# rc13-mbed-main-board.net
KiCad netlist of a schematic drawn in EAGLE
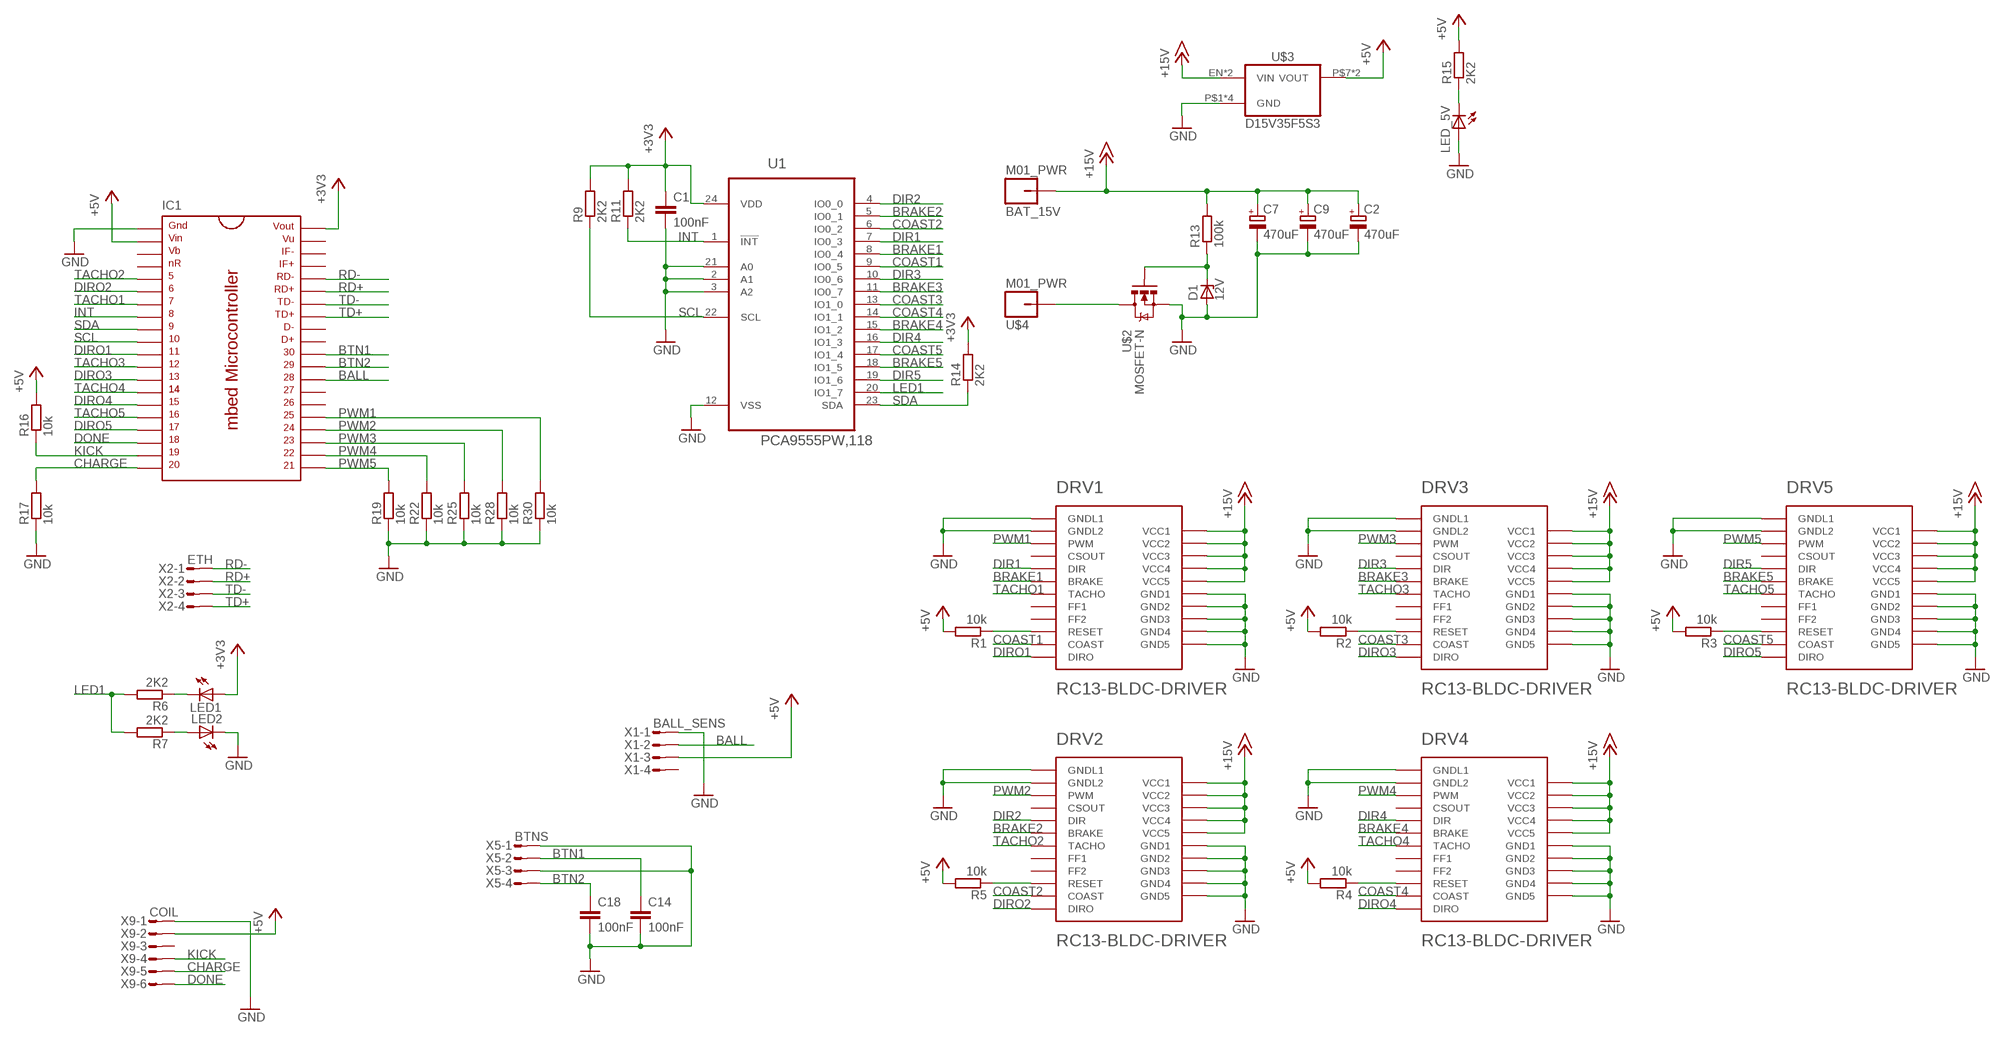
[diagram p0: schematic, sheet 1]

(export (version "E")
  (design (tool "Eeschema 10.0.6"))
  (components
    (comp (ref "BAT_15V")
      (value "M01_PWR")
      (footprint "eagle-import:PWR_HOLE")
      (libsource (lib "eagle-import") (part "M01_PWR"))
    )
    (comp (ref "C1")
      (value "100nF")
      (footprint "eagle-import:C0603K")
      (libsource (lib "eagle-import") (part "C-EUC0603K"))
    )
    (comp (ref "C2")
      (value "470uF")
      (footprint "eagle-import:E3,5-8")
      (libsource (lib "eagle-import") (part "CPOL-EUE3.5-8"))
    )
    (comp (ref "C7")
      (value "470uF")
      (footprint "eagle-import:E3,5-8")
      (libsource (lib "eagle-import") (part "CPOL-EUE3.5-8"))
    )
    (comp (ref "C9")
      (value "470uF")
      (footprint "eagle-import:E3,5-8")
      (libsource (lib "eagle-import") (part "CPOL-EUE3.5-8"))
    )
    (comp (ref "C14")
      (value "100nF")
      (footprint "eagle-import:C0603K")
      (libsource (lib "eagle-import") (part "C-EUC0603K"))
    )
    (comp (ref "C18")
      (value "100nF")
      (footprint "eagle-import:C0603K")
      (libsource (lib "eagle-import") (part "C-EUC0603K"))
    )
    (comp (ref "D1")
      (value "12V")
      (footprint "eagle-import:SOD123")
      (libsource (lib "eagle-import") (part "ZENER-DIODESOD123"))
    )
    (comp (ref "DRV1")
      (value "RC13-BLDC-DRIVER")
      (footprint "eagle-import:RC13-BLDC-DRIVER")
      (libsource (lib "eagle-import") (part "RC13-BLDC-DRIVER"))
    )
    (comp (ref "DRV2")
      (value "RC13-BLDC-DRIVER")
      (footprint "eagle-import:RC13-BLDC-DRIVER")
      (libsource (lib "eagle-import") (part "RC13-BLDC-DRIVER"))
    )
    (comp (ref "DRV3")
      (value "RC13-BLDC-DRIVER")
      (footprint "eagle-import:RC13-BLDC-DRIVER")
      (libsource (lib "eagle-import") (part "RC13-BLDC-DRIVER"))
    )
    (comp (ref "DRV4")
      (value "RC13-BLDC-DRIVER")
      (footprint "eagle-import:RC13-BLDC-DRIVER")
      (libsource (lib "eagle-import") (part "RC13-BLDC-DRIVER"))
    )
    (comp (ref "DRV5")
      (value "RC13-BLDC-DRIVER")
      (footprint "eagle-import:RC13-BLDC-DRIVER")
      (libsource (lib "eagle-import") (part "RC13-BLDC-DRIVER"))
    )
    (comp (ref "IC1")
      (value "MBED_MICROCONTROLLER")
      (footprint "eagle-import:DIL40_0.9")
      (libsource (lib "eagle-import") (part "MBED_MICROCONTROLLER"))
    )
    (comp (ref "LED1")
      (value "LEDCHIP-LED0603")
      (footprint "eagle-import:CHIP-LED0603")
      (libsource (lib "eagle-import") (part "LEDCHIP-LED0603"))
    )
    (comp (ref "LED2")
      (value "LEDCHIP-LED0603")
      (footprint "eagle-import:CHIP-LED0603")
      (libsource (lib "eagle-import") (part "LEDCHIP-LED0603"))
    )
    (comp (ref "LED_5V")
      (value "LEDCHIP-LED0603")
      (footprint "eagle-import:CHIP-LED0603")
      (libsource (lib "eagle-import") (part "LEDCHIP-LED0603"))
    )
    (comp (ref "R1")
      (value "10k")
      (footprint "eagle-import:R0603")
      (libsource (lib "eagle-import") (part "R-EU_R0603"))
    )
    (comp (ref "R2")
      (value "10k")
      (footprint "eagle-import:R0603")
      (libsource (lib "eagle-import") (part "R-EU_R0603"))
    )
    (comp (ref "R3")
      (value "10k")
      (footprint "eagle-import:R0603")
      (libsource (lib "eagle-import") (part "R-EU_R0603"))
    )
    (comp (ref "R4")
      (value "10k")
      (footprint "eagle-import:R0603")
      (libsource (lib "eagle-import") (part "R-EU_R0603"))
    )
    (comp (ref "R5")
      (value "10k")
      (footprint "eagle-import:R0603")
      (libsource (lib "eagle-import") (part "R-EU_R0603"))
    )
    (comp (ref "R6")
      (value "2K2")
      (footprint "eagle-import:R0603")
      (libsource (lib "eagle-import") (part "R-EU_R0603"))
    )
    (comp (ref "R7")
      (value "2K2")
      (footprint "eagle-import:R0603")
      (libsource (lib "eagle-import") (part "R-EU_R0603"))
    )
    (comp (ref "R9")
      (value "2K2")
      (footprint "eagle-import:R0603")
      (libsource (lib "eagle-import") (part "R-EU_R0603"))
    )
    (comp (ref "R11")
      (value "2K2")
      (footprint "eagle-import:R0603")
      (libsource (lib "eagle-import") (part "R-EU_R0603"))
    )
    (comp (ref "R13")
      (value "100k")
      (footprint "eagle-import:R0603")
      (libsource (lib "eagle-import") (part "R-EU_R0603"))
    )
    (comp (ref "R14")
      (value "2K2")
      (footprint "eagle-import:R0603")
      (libsource (lib "eagle-import") (part "R-EU_R0603"))
    )
    (comp (ref "R15")
      (value "2K2")
      (footprint "eagle-import:R0603")
      (libsource (lib "eagle-import") (part "R-EU_R0603"))
    )
    (comp (ref "R16")
      (value "10k")
      (footprint "eagle-import:R0603")
      (libsource (lib "eagle-import") (part "R-EU_R0603"))
    )
    (comp (ref "R17")
      (value "10k")
      (footprint "eagle-import:R0603")
      (libsource (lib "eagle-import") (part "R-EU_R0603"))
    )
    (comp (ref "R19")
      (value "10k")
      (footprint "eagle-import:R0603")
      (libsource (lib "eagle-import") (part "R-EU_R0603"))
    )
    (comp (ref "R22")
      (value "10k")
      (footprint "eagle-import:R0603")
      (libsource (lib "eagle-import") (part "R-EU_R0603"))
    )
    (comp (ref "R25")
      (value "10k")
      (footprint "eagle-import:R0603")
      (libsource (lib "eagle-import") (part "R-EU_R0603"))
    )
    (comp (ref "R28")
      (value "10k")
      (footprint "eagle-import:R0603")
      (libsource (lib "eagle-import") (part "R-EU_R0603"))
    )
    (comp (ref "R30")
      (value "10k")
      (footprint "eagle-import:R0603")
      (libsource (lib "eagle-import") (part "R-EU_R0603"))
    )
    (comp (ref "U$2")
      (value "MOSFET-N")
      (footprint "eagle-import:TO127P600X120-5N")
      (libsource (lib "eagle-import") (part "MOSFET-N-SOT669"))
    )
    (comp (ref "U$3")
      (value "D15V35F5S3")
      (footprint "eagle-import:D15V35F5S3")
      (libsource (lib "eagle-import") (part "D15V35F5S3"))
    )
    (comp (ref "U$4")
      (value "M01_PWR")
      (footprint "eagle-import:PWR_HOLE")
      (libsource (lib "eagle-import") (part "M01_PWR"))
    )
    (comp (ref "U1")
      (value "PCA9555PW,118")
      (footprint "eagle-import:SOP65P640X110-24N")
      (libsource (lib "eagle-import") (part "PCA9555PW,118"))
    )
    (comp (ref "X1")
      (value "BALL_SENS")
      (footprint "eagle-import:MICROMATCH-4")
      (fields (field (name "MPN") "7-215464-4"))
      (libsource (lib "eagle-import") (part "MICROMATCH-4"))
    )
    (comp (ref "X2")
      (value "ETH")
      (footprint "eagle-import:MICROMATCH-4")
      (fields (field (name "MPN") "7-215464-4"))
      (libsource (lib "eagle-import") (part "MICROMATCH-4"))
    )
    (comp (ref "X5")
      (value "BTNS")
      (footprint "eagle-import:MICROMATCH-4")
      (fields (field (name "MPN") "7-215464-4"))
      (libsource (lib "eagle-import") (part "MICROMATCH-4"))
    )
    (comp (ref "X9")
      (value "COIL")
      (footprint "eagle-import:MICROMATCH-6")
      (fields (field (name "MPN") "7-215464-6"))
      (libsource (lib "eagle-import") (part "MICROMATCH-6"))
    )
  )
  (nets
    (net (code "1") (name "+3V3") (class "Default")
      (node (ref "C1") (pin "1") (pinfunction "1_1") (pintype "passive"))
      (node (ref "IC1") (pin "40") (pinfunction "P$40_40") (pintype "bidirectional"))
      (node (ref "LED1") (pin "A") (pinfunction "A_A") (pintype "passive"))
      (node (ref "R11") (pin "2") (pinfunction "2_2") (pintype "passive"))
      (node (ref "R14") (pin "2") (pinfunction "2_2") (pintype "passive"))
      (node (ref "R9") (pin "2") (pinfunction "2_2") (pintype "passive"))
      (node (ref "U1") (pin "24") (pinfunction "VDD_24") (pintype "power_in"))
    )
    (net (code "2") (name "+5V") (class "Default")
      (node (ref "IC1") (pin "2") (pinfunction "P$2_2") (pintype "bidirectional"))
      (node (ref "R1") (pin "2") (pinfunction "2_2") (pintype "passive"))
      (node (ref "R15") (pin "2") (pinfunction "2_2") (pintype "passive"))
      (node (ref "R16") (pin "2") (pinfunction "2_2") (pintype "passive"))
      (node (ref "R2") (pin "2") (pinfunction "2_2") (pintype "passive"))
      (node (ref "R3") (pin "2") (pinfunction "2_2") (pintype "passive"))
      (node (ref "R4") (pin "2") (pinfunction "2_2") (pintype "passive"))
      (node (ref "R5") (pin "2") (pinfunction "2_2") (pintype "passive"))
      (node (ref "U$3") (pin "P$7") (pinfunction "VOUT_P$7") (pintype "power_in"))
      (node (ref "U$3") (pin "P$8") (pinfunction "VOUT_P$8") (pintype "power_in"))
      (node (ref "X1") (pin "3") (pinfunction "S_3") (pintype "passive"))
      (node (ref "X9") (pin "2") (pinfunction "S_2") (pintype "passive"))
    )
    (net (code "3") (name "+15V") (class "Default")
      (node (ref "BAT_15V") (pin "P$1") (pinfunction "P$1_P$1") (pintype "bidirectional"))
      (node (ref "C2") (pin "+") (pinfunction "+_+") (pintype "passive"))
      (node (ref "C7") (pin "+") (pinfunction "+_+") (pintype "passive"))
      (node (ref "C9") (pin "+") (pinfunction "+_+") (pintype "passive"))
      (node (ref "DRV1") (pin "PWR1") (pinfunction "VCC1_PWR1") (pintype "power_in"))
      (node (ref "DRV1") (pin "PWR2") (pinfunction "VCC2_PWR2") (pintype "power_in"))
      (node (ref "DRV1") (pin "PWR3") (pinfunction "VCC3_PWR3") (pintype "power_in"))
      (node (ref "DRV1") (pin "PWR4") (pinfunction "VCC4_PWR4") (pintype "power_in"))
      (node (ref "DRV1") (pin "PWR5") (pinfunction "VCC5_PWR5") (pintype "power_in"))
      (node (ref "DRV2") (pin "PWR1") (pinfunction "VCC1_PWR1") (pintype "power_in"))
      (node (ref "DRV2") (pin "PWR2") (pinfunction "VCC2_PWR2") (pintype "power_in"))
      (node (ref "DRV2") (pin "PWR3") (pinfunction "VCC3_PWR3") (pintype "power_in"))
      (node (ref "DRV2") (pin "PWR4") (pinfunction "VCC4_PWR4") (pintype "power_in"))
      (node (ref "DRV2") (pin "PWR5") (pinfunction "VCC5_PWR5") (pintype "power_in"))
      (node (ref "DRV3") (pin "PWR1") (pinfunction "VCC1_PWR1") (pintype "power_in"))
      (node (ref "DRV3") (pin "PWR2") (pinfunction "VCC2_PWR2") (pintype "power_in"))
      (node (ref "DRV3") (pin "PWR3") (pinfunction "VCC3_PWR3") (pintype "power_in"))
      (node (ref "DRV3") (pin "PWR4") (pinfunction "VCC4_PWR4") (pintype "power_in"))
      (node (ref "DRV3") (pin "PWR5") (pinfunction "VCC5_PWR5") (pintype "power_in"))
      (node (ref "DRV4") (pin "PWR1") (pinfunction "VCC1_PWR1") (pintype "power_in"))
      (node (ref "DRV4") (pin "PWR2") (pinfunction "VCC2_PWR2") (pintype "power_in"))
      (node (ref "DRV4") (pin "PWR3") (pinfunction "VCC3_PWR3") (pintype "power_in"))
      (node (ref "DRV4") (pin "PWR4") (pinfunction "VCC4_PWR4") (pintype "power_in"))
      (node (ref "DRV4") (pin "PWR5") (pinfunction "VCC5_PWR5") (pintype "power_in"))
      (node (ref "DRV5") (pin "PWR1") (pinfunction "VCC1_PWR1") (pintype "power_in"))
      (node (ref "DRV5") (pin "PWR2") (pinfunction "VCC2_PWR2") (pintype "power_in"))
      (node (ref "DRV5") (pin "PWR3") (pinfunction "VCC3_PWR3") (pintype "power_in"))
      (node (ref "DRV5") (pin "PWR4") (pinfunction "VCC4_PWR4") (pintype "power_in"))
      (node (ref "DRV5") (pin "PWR5") (pinfunction "VCC5_PWR5") (pintype "power_in"))
      (node (ref "R13") (pin "2") (pinfunction "2_2") (pintype "passive"))
      (node (ref "U$3") (pin "EN") (pinfunction "VIN_EN") (pintype "power_in"))
      (node (ref "U$3") (pin "P$5") (pinfunction "VIN_P$5") (pintype "power_in"))
    )
    (net (code "4") (name "/BALL") (class "Default")
      (node (ref "IC1") (pin "28") (pinfunction "P$28_28") (pintype "bidirectional"))
      (node (ref "X1") (pin "2") (pinfunction "S_2") (pintype "passive"))
    )
    (net (code "5") (name "/BRAKE1") (class "Default")
      (node (ref "DRV1") (pin "LOGIC6") (pinfunction "BRAKE_LOGIC6") (pintype "input"))
      (node (ref "U1") (pin "8") (pinfunction "IO0_4_8") (pintype "bidirectional"))
    )
    (net (code "6") (name "/BRAKE2") (class "Default")
      (node (ref "DRV2") (pin "LOGIC6") (pinfunction "BRAKE_LOGIC6") (pintype "input"))
      (node (ref "U1") (pin "5") (pinfunction "IO0_1_5") (pintype "bidirectional"))
    )
    (net (code "7") (name "/BRAKE3") (class "Default")
      (node (ref "DRV3") (pin "LOGIC6") (pinfunction "BRAKE_LOGIC6") (pintype "input"))
      (node (ref "U1") (pin "11") (pinfunction "IO0_7_11") (pintype "bidirectional"))
    )
    (net (code "8") (name "/BRAKE4") (class "Default")
      (node (ref "DRV4") (pin "LOGIC6") (pinfunction "BRAKE_LOGIC6") (pintype "input"))
      (node (ref "U1") (pin "15") (pinfunction "IO1_2_15") (pintype "bidirectional"))
    )
    (net (code "9") (name "/BRAKE5") (class "Default")
      (node (ref "DRV5") (pin "LOGIC6") (pinfunction "BRAKE_LOGIC6") (pintype "input"))
      (node (ref "U1") (pin "18") (pinfunction "IO1_5_18") (pintype "bidirectional"))
    )
    (net (code "10") (name "/BTN1") (class "Default")
      (node (ref "C14") (pin "1") (pinfunction "1_1") (pintype "passive"))
      (node (ref "IC1") (pin "30") (pinfunction "P$30_30") (pintype "bidirectional"))
      (node (ref "X5") (pin "2") (pinfunction "S_2") (pintype "passive"))
    )
    (net (code "11") (name "/BTN2") (class "Default")
      (node (ref "C18") (pin "1") (pinfunction "1_1") (pintype "passive"))
      (node (ref "IC1") (pin "29") (pinfunction "P$29_29") (pintype "bidirectional"))
      (node (ref "X5") (pin "4") (pinfunction "S_4") (pintype "passive"))
    )
    (net (code "12") (name "/CHARGE") (class "Default")
      (node (ref "IC1") (pin "20") (pinfunction "P$20_20") (pintype "bidirectional"))
      (node (ref "R17") (pin "2") (pinfunction "2_2") (pintype "passive"))
      (node (ref "X9") (pin "5") (pinfunction "S_5") (pintype "passive"))
    )
    (net (code "13") (name "/COAST1") (class "Default")
      (node (ref "DRV1") (pin "LOGIC11") (pinfunction "COAST_LOGIC11") (pintype "input"))
      (node (ref "U1") (pin "9") (pinfunction "IO0_5_9") (pintype "bidirectional"))
    )
    (net (code "14") (name "/COAST2") (class "Default")
      (node (ref "DRV2") (pin "LOGIC11") (pinfunction "COAST_LOGIC11") (pintype "input"))
      (node (ref "U1") (pin "6") (pinfunction "IO0_2_6") (pintype "bidirectional"))
    )
    (net (code "15") (name "/COAST3") (class "Default")
      (node (ref "DRV3") (pin "LOGIC11") (pinfunction "COAST_LOGIC11") (pintype "input"))
      (node (ref "U1") (pin "13") (pinfunction "IO1_0_13") (pintype "bidirectional"))
    )
    (net (code "16") (name "/COAST4") (class "Default")
      (node (ref "DRV4") (pin "LOGIC11") (pinfunction "COAST_LOGIC11") (pintype "input"))
      (node (ref "U1") (pin "14") (pinfunction "IO1_1_14") (pintype "bidirectional"))
    )
    (net (code "17") (name "/COAST5") (class "Default")
      (node (ref "DRV5") (pin "LOGIC11") (pinfunction "COAST_LOGIC11") (pintype "input"))
      (node (ref "U1") (pin "17") (pinfunction "IO1_4_17") (pintype "bidirectional"))
    )
    (net (code "18") (name "/DIR1") (class "Default")
      (node (ref "DRV1") (pin "LOGIC5") (pinfunction "DIR_LOGIC5") (pintype "input"))
      (node (ref "U1") (pin "7") (pinfunction "IO0_3_7") (pintype "bidirectional"))
    )
    (net (code "19") (name "/DIR2") (class "Default")
      (node (ref "DRV2") (pin "LOGIC5") (pinfunction "DIR_LOGIC5") (pintype "input"))
      (node (ref "U1") (pin "4") (pinfunction "IO0_0_4") (pintype "bidirectional"))
    )
    (net (code "20") (name "/DIR3") (class "Default")
      (node (ref "DRV3") (pin "LOGIC5") (pinfunction "DIR_LOGIC5") (pintype "input"))
      (node (ref "U1") (pin "10") (pinfunction "IO0_6_10") (pintype "bidirectional"))
    )
    (net (code "21") (name "/DIR4") (class "Default")
      (node (ref "DRV4") (pin "LOGIC5") (pinfunction "DIR_LOGIC5") (pintype "input"))
      (node (ref "U1") (pin "16") (pinfunction "IO1_3_16") (pintype "bidirectional"))
    )
    (net (code "22") (name "/DIR5") (class "Default")
      (node (ref "DRV5") (pin "LOGIC5") (pinfunction "DIR_LOGIC5") (pintype "input"))
      (node (ref "U1") (pin "19") (pinfunction "IO1_6_19") (pintype "bidirectional"))
    )
    (net (code "23") (name "/DIRO1") (class "Default")
      (node (ref "DRV1") (pin "LOGIC12") (pinfunction "DIRO_LOGIC12") (pintype "output"))
      (node (ref "IC1") (pin "11") (pinfunction "P$11_11") (pintype "bidirectional"))
    )
    (net (code "24") (name "/DIRO2") (class "Default")
      (node (ref "DRV2") (pin "LOGIC12") (pinfunction "DIRO_LOGIC12") (pintype "output"))
      (node (ref "IC1") (pin "6") (pinfunction "P$6_6") (pintype "bidirectional"))
    )
    (net (code "25") (name "/DIRO3") (class "Default")
      (node (ref "DRV3") (pin "LOGIC12") (pinfunction "DIRO_LOGIC12") (pintype "output"))
      (node (ref "IC1") (pin "13") (pinfunction "P$13_13") (pintype "bidirectional"))
    )
    (net (code "26") (name "/DIRO4") (class "Default")
      (node (ref "DRV4") (pin "LOGIC12") (pinfunction "DIRO_LOGIC12") (pintype "output"))
      (node (ref "IC1") (pin "15") (pinfunction "P$15_15") (pintype "bidirectional"))
    )
    (net (code "27") (name "/DIRO5") (class "Default")
      (node (ref "DRV5") (pin "LOGIC12") (pinfunction "DIRO_LOGIC12") (pintype "output"))
      (node (ref "IC1") (pin "17") (pinfunction "P$17_17") (pintype "bidirectional"))
    )
    (net (code "28") (name "/DONE") (class "Default")
      (node (ref "IC1") (pin "18") (pinfunction "P$18_18") (pintype "bidirectional"))
      (node (ref "X9") (pin "6") (pinfunction "S_6") (pintype "passive"))
    )
    (net (code "29") (name "/INT") (class "Default")
      (node (ref "IC1") (pin "8") (pinfunction "P$8_8") (pintype "bidirectional"))
      (node (ref "R11") (pin "1") (pinfunction "1_1") (pintype "passive"))
      (node (ref "U1") (pin "1") (pinfunction "~{INT}_1") (pintype "output"))
    )
    (net (code "30") (name "/KICK") (class "Default")
      (node (ref "IC1") (pin "19") (pinfunction "P$19_19") (pintype "bidirectional"))
      (node (ref "R16") (pin "1") (pinfunction "1_1") (pintype "passive"))
      (node (ref "X9") (pin "4") (pinfunction "S_4") (pintype "passive"))
    )
    (net (code "31") (name "/LED1") (class "Default")
      (node (ref "R6") (pin "2") (pinfunction "2_2") (pintype "passive"))
      (node (ref "R7") (pin "2") (pinfunction "2_2") (pintype "passive"))
      (node (ref "U1") (pin "20") (pinfunction "IO1_7_20") (pintype "bidirectional"))
    )
    (net (code "32") (name "/PWM1") (class "Default")
      (node (ref "DRV1") (pin "LOGIC3") (pinfunction "PWM_LOGIC3") (pintype "input"))
      (node (ref "IC1") (pin "25") (pinfunction "P$25_25") (pintype "bidirectional"))
      (node (ref "R30") (pin "2") (pinfunction "2_2") (pintype "passive"))
    )
    (net (code "33") (name "/PWM2") (class "Default")
      (node (ref "DRV2") (pin "LOGIC3") (pinfunction "PWM_LOGIC3") (pintype "input"))
      (node (ref "IC1") (pin "24") (pinfunction "P$24_24") (pintype "bidirectional"))
      (node (ref "R28") (pin "2") (pinfunction "2_2") (pintype "passive"))
    )
    (net (code "34") (name "/PWM3") (class "Default")
      (node (ref "DRV3") (pin "LOGIC3") (pinfunction "PWM_LOGIC3") (pintype "input"))
      (node (ref "IC1") (pin "23") (pinfunction "P$23_23") (pintype "bidirectional"))
      (node (ref "R25") (pin "2") (pinfunction "2_2") (pintype "passive"))
    )
    (net (code "35") (name "/PWM4") (class "Default")
      (node (ref "DRV4") (pin "LOGIC3") (pinfunction "PWM_LOGIC3") (pintype "input"))
      (node (ref "IC1") (pin "22") (pinfunction "P$22_22") (pintype "bidirectional"))
      (node (ref "R22") (pin "2") (pinfunction "2_2") (pintype "passive"))
    )
    (net (code "36") (name "/PWM5") (class "Default")
      (node (ref "DRV5") (pin "LOGIC3") (pinfunction "PWM_LOGIC3") (pintype "input"))
      (node (ref "IC1") (pin "21") (pinfunction "P$21_21") (pintype "bidirectional"))
      (node (ref "R19") (pin "2") (pinfunction "2_2") (pintype "passive"))
    )
    (net (code "37") (name "/RD+") (class "Default")
      (node (ref "IC1") (pin "35") (pinfunction "P$35_35") (pintype "bidirectional"))
      (node (ref "X2") (pin "2") (pinfunction "S_2") (pintype "passive"))
    )
    (net (code "38") (name "/RD-") (class "Default")
      (node (ref "IC1") (pin "36") (pinfunction "P$36_36") (pintype "bidirectional"))
      (node (ref "X2") (pin "1") (pinfunction "S_1") (pintype "passive"))
    )
    (net (code "39") (name "/SCL") (class "Default")
      (node (ref "IC1") (pin "10") (pinfunction "P$10_10") (pintype "bidirectional"))
      (node (ref "R9") (pin "1") (pinfunction "1_1") (pintype "passive"))
      (node (ref "U1") (pin "22") (pinfunction "SCL_22") (pintype "input"))
    )
    (net (code "40") (name "/SDA") (class "Default")
      (node (ref "IC1") (pin "9") (pinfunction "P$9_9") (pintype "bidirectional"))
      (node (ref "R14") (pin "1") (pinfunction "1_1") (pintype "passive"))
      (node (ref "U1") (pin "23") (pinfunction "SDA_23") (pintype "bidirectional"))
    )
    (net (code "41") (name "/TACHO1") (class "Default")
      (node (ref "DRV1") (pin "LOGIC7") (pinfunction "TACHO_LOGIC7") (pintype "output"))
      (node (ref "IC1") (pin "7") (pinfunction "P$7_7") (pintype "bidirectional"))
    )
    (net (code "42") (name "/TACHO2") (class "Default")
      (node (ref "DRV2") (pin "LOGIC7") (pinfunction "TACHO_LOGIC7") (pintype "output"))
      (node (ref "IC1") (pin "5") (pinfunction "P$5_5") (pintype "bidirectional"))
    )
    (net (code "43") (name "/TACHO3") (class "Default")
      (node (ref "DRV3") (pin "LOGIC7") (pinfunction "TACHO_LOGIC7") (pintype "output"))
      (node (ref "IC1") (pin "12") (pinfunction "P$12_12") (pintype "bidirectional"))
    )
    (net (code "44") (name "/TACHO4") (class "Default")
      (node (ref "DRV4") (pin "LOGIC7") (pinfunction "TACHO_LOGIC7") (pintype "output"))
      (node (ref "IC1") (pin "14") (pinfunction "P$14_14") (pintype "bidirectional"))
    )
    (net (code "45") (name "/TACHO5") (class "Default")
      (node (ref "DRV5") (pin "LOGIC7") (pinfunction "TACHO_LOGIC7") (pintype "output"))
      (node (ref "IC1") (pin "16") (pinfunction "P$16_16") (pintype "bidirectional"))
    )
    (net (code "46") (name "/TD+") (class "Default")
      (node (ref "IC1") (pin "33") (pinfunction "P$33_33") (pintype "bidirectional"))
      (node (ref "X2") (pin "4") (pinfunction "S_4") (pintype "passive"))
    )
    (net (code "47") (name "/TD-") (class "Default")
      (node (ref "IC1") (pin "34") (pinfunction "P$34_34") (pintype "bidirectional"))
      (node (ref "X2") (pin "3") (pinfunction "S_3") (pintype "passive"))
    )
    (net (code "48") (name "GND") (class "Default")
      (node (ref "C1") (pin "2") (pinfunction "2_2") (pintype "passive"))
      (node (ref "C14") (pin "2") (pinfunction "2_2") (pintype "passive"))
      (node (ref "C18") (pin "2") (pinfunction "2_2") (pintype "passive"))
      (node (ref "C2") (pin "-") (pinfunction "-_-") (pintype "passive"))
      (node (ref "C7") (pin "-") (pinfunction "-_-") (pintype "passive"))
      (node (ref "C9") (pin "-") (pinfunction "-_-") (pintype "passive"))
      (node (ref "D1") (pin "A") (pinfunction "A_A") (pintype "passive"))
      (node (ref "DRV1") (pin "LOGIC1") (pinfunction "GNDL1_LOGIC1") (pintype "power_in"))
      (node (ref "DRV1") (pin "LOGIC2") (pinfunction "GNDL2_LOGIC2") (pintype "power_in"))
      (node (ref "DRV1") (pin "PWR10") (pinfunction "GND5_PWR10") (pintype "power_in"))
      (node (ref "DRV1") (pin "PWR6") (pinfunction "GND1_PWR6") (pintype "power_in"))
      (node (ref "DRV1") (pin "PWR7") (pinfunction "GND2_PWR7") (pintype "power_in"))
      (node (ref "DRV1") (pin "PWR8") (pinfunction "GND3_PWR8") (pintype "power_in"))
      (node (ref "DRV1") (pin "PWR9") (pinfunction "GND4_PWR9") (pintype "power_in"))
      (node (ref "DRV2") (pin "LOGIC1") (pinfunction "GNDL1_LOGIC1") (pintype "power_in"))
      (node (ref "DRV2") (pin "LOGIC2") (pinfunction "GNDL2_LOGIC2") (pintype "power_in"))
      (node (ref "DRV2") (pin "PWR10") (pinfunction "GND5_PWR10") (pintype "power_in"))
      (node (ref "DRV2") (pin "PWR6") (pinfunction "GND1_PWR6") (pintype "power_in"))
      (node (ref "DRV2") (pin "PWR7") (pinfunction "GND2_PWR7") (pintype "power_in"))
      (node (ref "DRV2") (pin "PWR8") (pinfunction "GND3_PWR8") (pintype "power_in"))
      (node (ref "DRV2") (pin "PWR9") (pinfunction "GND4_PWR9") (pintype "power_in"))
      (node (ref "DRV3") (pin "LOGIC1") (pinfunction "GNDL1_LOGIC1") (pintype "power_in"))
      (node (ref "DRV3") (pin "LOGIC2") (pinfunction "GNDL2_LOGIC2") (pintype "power_in"))
      (node (ref "DRV3") (pin "PWR10") (pinfunction "GND5_PWR10") (pintype "power_in"))
      (node (ref "DRV3") (pin "PWR6") (pinfunction "GND1_PWR6") (pintype "power_in"))
      (node (ref "DRV3") (pin "PWR7") (pinfunction "GND2_PWR7") (pintype "power_in"))
      (node (ref "DRV3") (pin "PWR8") (pinfunction "GND3_PWR8") (pintype "power_in"))
      (node (ref "DRV3") (pin "PWR9") (pinfunction "GND4_PWR9") (pintype "power_in"))
      (node (ref "DRV4") (pin "LOGIC1") (pinfunction "GNDL1_LOGIC1") (pintype "power_in"))
      (node (ref "DRV4") (pin "LOGIC2") (pinfunction "GNDL2_LOGIC2") (pintype "power_in"))
      (node (ref "DRV4") (pin "PWR10") (pinfunction "GND5_PWR10") (pintype "power_in"))
      (node (ref "DRV4") (pin "PWR6") (pinfunction "GND1_PWR6") (pintype "power_in"))
      (node (ref "DRV4") (pin "PWR7") (pinfunction "GND2_PWR7") (pintype "power_in"))
      (node (ref "DRV4") (pin "PWR8") (pinfunction "GND3_PWR8") (pintype "power_in"))
      (node (ref "DRV4") (pin "PWR9") (pinfunction "GND4_PWR9") (pintype "power_in"))
      (node (ref "DRV5") (pin "LOGIC1") (pinfunction "GNDL1_LOGIC1") (pintype "power_in"))
      (node (ref "DRV5") (pin "LOGIC2") (pinfunction "GNDL2_LOGIC2") (pintype "power_in"))
      (node (ref "DRV5") (pin "PWR10") (pinfunction "GND5_PWR10") (pintype "power_in"))
      (node (ref "DRV5") (pin "PWR6") (pinfunction "GND1_PWR6") (pintype "power_in"))
      (node (ref "DRV5") (pin "PWR7") (pinfunction "GND2_PWR7") (pintype "power_in"))
      (node (ref "DRV5") (pin "PWR8") (pinfunction "GND3_PWR8") (pintype "power_in"))
      (node (ref "DRV5") (pin "PWR9") (pinfunction "GND4_PWR9") (pintype "power_in"))
      (node (ref "IC1") (pin "1") (pinfunction "P$1_1") (pintype "bidirectional"))
      (node (ref "LED2") (pin "C") (pinfunction "C_C") (pintype "passive"))
      (node (ref "LED_5V") (pin "A") (pinfunction "A_A") (pintype "passive"))
      (node (ref "R17") (pin "1") (pinfunction "1_1") (pintype "passive"))
      (node (ref "R19") (pin "1") (pinfunction "1_1") (pintype "passive"))
      (node (ref "R22") (pin "1") (pinfunction "1_1") (pintype "passive"))
      (node (ref "R25") (pin "1") (pinfunction "1_1") (pintype "passive"))
      (node (ref "R28") (pin "1") (pinfunction "1_1") (pintype "passive"))
      (node (ref "R30") (pin "1") (pinfunction "1_1") (pintype "passive"))
      (node (ref "U$2") (pin "1") (pinfunction "S_1") (pintype "passive"))
      (node (ref "U$2") (pin "2") (pinfunction "S_2") (pintype "passive"))
      (node (ref "U$2") (pin "3") (pinfunction "S_3") (pintype "passive"))
      (node (ref "U$3") (pin "P$1") (pinfunction "GND_P$1") (pintype "power_in"))
      (node (ref "U$3") (pin "P$2") (pinfunction "GND_P$2") (pintype "power_in"))
      (node (ref "U$3") (pin "P$3") (pinfunction "GND_P$3") (pintype "power_in"))
      (node (ref "U$3") (pin "P$4") (pinfunction "GND_P$4") (pintype "power_in"))
      (node (ref "U1") (pin "12") (pinfunction "VSS_12") (pintype "power_in"))
      (node (ref "U1") (pin "2") (pinfunction "A1_2") (pintype "input"))
      (node (ref "U1") (pin "21") (pinfunction "A0_21") (pintype "input"))
      (node (ref "U1") (pin "3") (pinfunction "A2_3") (pintype "input"))
      (node (ref "X1") (pin "1") (pinfunction "S_1") (pintype "passive"))
      (node (ref "X5") (pin "1") (pinfunction "S_1") (pintype "passive"))
      (node (ref "X5") (pin "3") (pinfunction "S_3") (pintype "passive"))
      (node (ref "X9") (pin "1") (pinfunction "S_1") (pintype "passive"))
    )
    (net (code "49") (name "Net-(DRV1-RESET)") (class "Default")
      (node (ref "DRV1") (pin "LOGIC10") (pinfunction "RESET_LOGIC10") (pintype "input"))
      (node (ref "R1") (pin "1") (pinfunction "1_1") (pintype "passive"))
    )
    (net (code "50") (name "Net-(DRV2-RESET)") (class "Default")
      (node (ref "DRV2") (pin "LOGIC10") (pinfunction "RESET_LOGIC10") (pintype "input"))
      (node (ref "R5") (pin "1") (pinfunction "1_1") (pintype "passive"))
    )
    (net (code "51") (name "Net-(DRV3-RESET)") (class "Default")
      (node (ref "DRV3") (pin "LOGIC10") (pinfunction "RESET_LOGIC10") (pintype "input"))
      (node (ref "R2") (pin "1") (pinfunction "1_1") (pintype "passive"))
    )
    (net (code "52") (name "Net-(DRV4-RESET)") (class "Default")
      (node (ref "DRV4") (pin "LOGIC10") (pinfunction "RESET_LOGIC10") (pintype "input"))
      (node (ref "R4") (pin "1") (pinfunction "1_1") (pintype "passive"))
    )
    (net (code "53") (name "Net-(DRV5-RESET)") (class "Default")
      (node (ref "DRV5") (pin "LOGIC10") (pinfunction "RESET_LOGIC10") (pintype "input"))
      (node (ref "R3") (pin "1") (pinfunction "1_1") (pintype "passive"))
    )
    (net (code "54") (name "Net-(LED1-PadC)") (class "Default")
      (node (ref "LED1") (pin "C") (pinfunction "C_C") (pintype "passive"))
      (node (ref "R6") (pin "1") (pinfunction "1_1") (pintype "passive"))
    )
    (net (code "55") (name "Net-(LED2-PadA)") (class "Default")
      (node (ref "LED2") (pin "A") (pinfunction "A_A") (pintype "passive"))
      (node (ref "R7") (pin "1") (pinfunction "1_1") (pintype "passive"))
    )
    (net (code "56") (name "Net-(LED_5V-PadC)") (class "Default")
      (node (ref "LED_5V") (pin "C") (pinfunction "C_C") (pintype "passive"))
      (node (ref "R15") (pin "1") (pinfunction "1_1") (pintype "passive"))
    )
    (net (code "57") (name "Net-(U$2-D)") (class "Default")
      (node (ref "U$2") (pin "5") (pinfunction "D_5") (pintype "passive"))
      (node (ref "U$4") (pin "P$1") (pinfunction "P$1_P$1") (pintype "bidirectional"))
    )
    (net (code "58") (name "Net-(U$2-G)") (class "Default")
      (node (ref "D1") (pin "C") (pinfunction "C_C") (pintype "passive"))
      (node (ref "R13") (pin "1") (pinfunction "1_1") (pintype "passive"))
      (node (ref "U$2") (pin "4") (pinfunction "G_4") (pintype "passive"))
    )
    (net (code "59") (name "unconnected-(DRV1-CSOUT-PadLOGIC4)") (class "Default")
      (node (ref "DRV1") (pin "LOGIC4") (pinfunction "CSOUT_LOGIC4") (pintype "output"))
    )
    (net (code "60") (name "unconnected-(DRV1-FF1-PadLOGIC8)") (class "Default")
      (node (ref "DRV1") (pin "LOGIC8") (pinfunction "FF1_LOGIC8") (pintype "output"))
    )
    (net (code "61") (name "unconnected-(DRV1-FF2-PadLOGIC9)") (class "Default")
      (node (ref "DRV1") (pin "LOGIC9") (pinfunction "FF2_LOGIC9") (pintype "output"))
    )
    (net (code "62") (name "unconnected-(DRV2-CSOUT-PadLOGIC4)") (class "Default")
      (node (ref "DRV2") (pin "LOGIC4") (pinfunction "CSOUT_LOGIC4") (pintype "output"))
    )
    (net (code "63") (name "unconnected-(DRV2-FF1-PadLOGIC8)") (class "Default")
      (node (ref "DRV2") (pin "LOGIC8") (pinfunction "FF1_LOGIC8") (pintype "output"))
    )
    (net (code "64") (name "unconnected-(DRV2-FF2-PadLOGIC9)") (class "Default")
      (node (ref "DRV2") (pin "LOGIC9") (pinfunction "FF2_LOGIC9") (pintype "output"))
    )
    (net (code "65") (name "unconnected-(DRV3-CSOUT-PadLOGIC4)") (class "Default")
      (node (ref "DRV3") (pin "LOGIC4") (pinfunction "CSOUT_LOGIC4") (pintype "output"))
    )
    (net (code "66") (name "unconnected-(DRV3-FF1-PadLOGIC8)") (class "Default")
      (node (ref "DRV3") (pin "LOGIC8") (pinfunction "FF1_LOGIC8") (pintype "output"))
    )
    (net (code "67") (name "unconnected-(DRV3-FF2-PadLOGIC9)") (class "Default")
      (node (ref "DRV3") (pin "LOGIC9") (pinfunction "FF2_LOGIC9") (pintype "output"))
    )
    (net (code "68") (name "unconnected-(DRV4-CSOUT-PadLOGIC4)") (class "Default")
      (node (ref "DRV4") (pin "LOGIC4") (pinfunction "CSOUT_LOGIC4") (pintype "output"))
    )
    (net (code "69") (name "unconnected-(DRV4-FF1-PadLOGIC8)") (class "Default")
      (node (ref "DRV4") (pin "LOGIC8") (pinfunction "FF1_LOGIC8") (pintype "output"))
    )
    (net (code "70") (name "unconnected-(DRV4-FF2-PadLOGIC9)") (class "Default")
      (node (ref "DRV4") (pin "LOGIC9") (pinfunction "FF2_LOGIC9") (pintype "output"))
    )
    (net (code "71") (name "unconnected-(DRV5-CSOUT-PadLOGIC4)") (class "Default")
      (node (ref "DRV5") (pin "LOGIC4") (pinfunction "CSOUT_LOGIC4") (pintype "output"))
    )
    (net (code "72") (name "unconnected-(DRV5-FF1-PadLOGIC8)") (class "Default")
      (node (ref "DRV5") (pin "LOGIC8") (pinfunction "FF1_LOGIC8") (pintype "output"))
    )
    (net (code "73") (name "unconnected-(DRV5-FF2-PadLOGIC9)") (class "Default")
      (node (ref "DRV5") (pin "LOGIC9") (pinfunction "FF2_LOGIC9") (pintype "output"))
    )
    (net (code "74") (name "unconnected-(IC1-P$3-Pad3)") (class "Default")
      (node (ref "IC1") (pin "3") (pinfunction "P$3_3") (pintype "bidirectional"))
    )
    (net (code "75") (name "unconnected-(IC1-P$4-Pad4)") (class "Default")
      (node (ref "IC1") (pin "4") (pinfunction "P$4_4") (pintype "bidirectional"))
    )
    (net (code "76") (name "unconnected-(IC1-P$26-Pad26)") (class "Default")
      (node (ref "IC1") (pin "26") (pinfunction "P$26_26") (pintype "bidirectional"))
    )
    (net (code "77") (name "unconnected-(IC1-P$27-Pad27)") (class "Default")
      (node (ref "IC1") (pin "27") (pinfunction "P$27_27") (pintype "bidirectional"))
    )
    (net (code "78") (name "unconnected-(IC1-P$31-Pad31)") (class "Default")
      (node (ref "IC1") (pin "31") (pinfunction "P$31_31") (pintype "bidirectional"))
    )
    (net (code "79") (name "unconnected-(IC1-P$32-Pad32)") (class "Default")
      (node (ref "IC1") (pin "32") (pinfunction "P$32_32") (pintype "bidirectional"))
    )
    (net (code "80") (name "unconnected-(IC1-P$37-Pad37)") (class "Default")
      (node (ref "IC1") (pin "37") (pinfunction "P$37_37") (pintype "bidirectional"))
    )
    (net (code "81") (name "unconnected-(IC1-P$38-Pad38)") (class "Default")
      (node (ref "IC1") (pin "38") (pinfunction "P$38_38") (pintype "bidirectional"))
    )
    (net (code "82") (name "unconnected-(IC1-P$39-Pad39)") (class "Default")
      (node (ref "IC1") (pin "39") (pinfunction "P$39_39") (pintype "bidirectional"))
    )
    (net (code "83") (name "unconnected-(X1D-S-Pad4)") (class "Default")
      (node (ref "X1") (pin "4") (pinfunction "S_4") (pintype "passive"))
    )
    (net (code "84") (name "unconnected-(X9C-S-Pad3)") (class "Default")
      (node (ref "X9") (pin "3") (pinfunction "S_3") (pintype "passive"))
    )
  )
)
